# xm125_testing.net
KiCad netlist of a schematic drawn in EAGLE
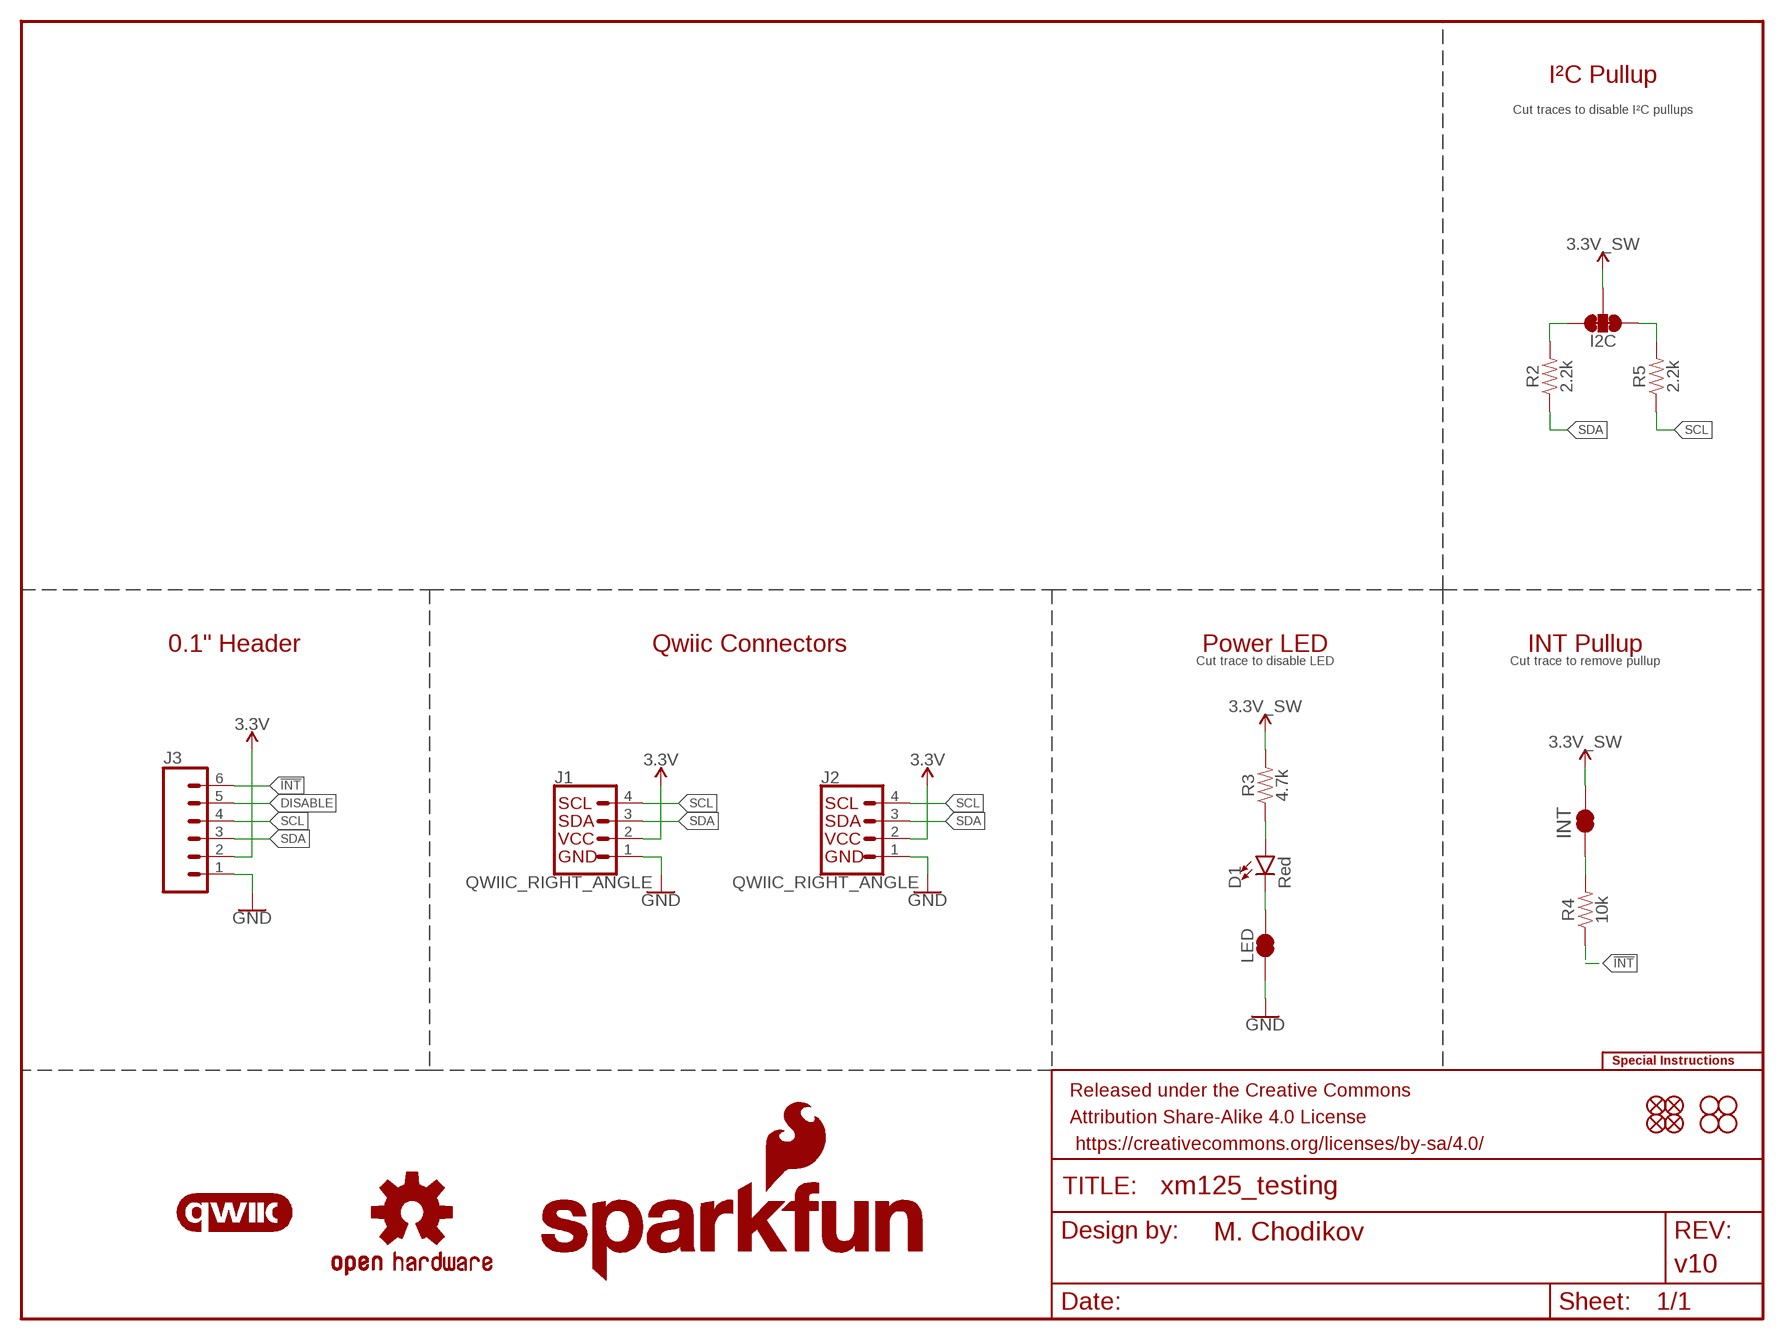
[diagram p0: schematic, sheet 1]

(export (version "E")
  (design (tool "Eeschema 10.0.6"))
  (components
    (comp (ref "D1")
      (value "Red")
      (footprint "eagle-import:LED-0603")
      (libsource (lib "eagle-import") (part "LED-RED_0603-KB"))
    )
    (comp (ref "FD1")
      (value "FIDUCIAL1X2")
      (footprint "eagle-import:FIDUCIAL-1X2")
      (libsource (lib "eagle-import") (part "FIDUCIAL1X2"))
    )
    (comp (ref "FD2")
      (value "FIDUCIAL1X2")
      (footprint "eagle-import:FIDUCIAL-1X2")
      (libsource (lib "eagle-import") (part "FIDUCIAL1X2"))
    )
    (comp (ref "FD3")
      (value "FIDUCIAL1X2")
      (footprint "eagle-import:FIDUCIAL-1X2")
      (libsource (lib "eagle-import") (part "FIDUCIAL1X2"))
    )
    (comp (ref "FD4")
      (value "FIDUCIAL1X2")
      (footprint "eagle-import:FIDUCIAL-1X2")
      (libsource (lib "eagle-import") (part "FIDUCIAL1X2"))
    )
    (comp (ref "FRAME1")
      (value "FRAME-LETTER")
      (footprint "eagle-import:CREATIVE_COMMONS")
      (fields (field (name "DESIGNER") "M. Chodikov") (field (name "REV") "v10"))
      (libsource (lib "eagle-import") (part "FRAME-LETTER"))
    )
    (comp (ref "H1")
      (value "STAND-OFF")
      (footprint "eagle-import:STAND-OFF")
      (libsource (lib "eagle-import") (part "STAND-OFF"))
    )
    (comp (ref "H2")
      (value "STAND-OFF")
      (footprint "eagle-import:STAND-OFF")
      (libsource (lib "eagle-import") (part "STAND-OFF"))
    )
    (comp (ref "H3")
      (value "STAND-OFF")
      (footprint "eagle-import:STAND-OFF")
      (libsource (lib "eagle-import") (part "STAND-OFF"))
    )
    (comp (ref "H4")
      (value "STAND-OFF")
      (footprint "eagle-import:STAND-OFF")
      (libsource (lib "eagle-import") (part "STAND-OFF"))
    )
    (comp (ref "I2C")
      (value "JUMPER-SMT_3_2-NC_TRACE_SILK")
      (footprint "eagle-import:SMT-JUMPER_3_2-NC_TRACE_SILK")
      (libsource (lib "eagle-import") (part "JUMPER-SMT_3_2-NC_TRACE_SILK"))
    )
    (comp (ref "J1")
      (value "QWIIC_RIGHT_ANGLE")
      (footprint "eagle-import:JST04_1MM_RA")
      (libsource (lib "eagle-import") (part "QWIIC_CONNECTORJS-1MM"))
    )
    (comp (ref "J2")
      (value "QWIIC_RIGHT_ANGLE")
      (footprint "eagle-import:JST04_1MM_RA")
      (libsource (lib "eagle-import") (part "QWIIC_CONNECTORJS-1MM"))
    )
    (comp (ref "J3")
      (value "CONN_06NO_SILK_FEMALE_PTH")
      (footprint "eagle-import:1X06_NO_SILK")
      (libsource (lib "eagle-import") (part "CONN_06NO_SILK_FEMALE_PTH"))
    )
    (comp (ref "JP2")
      (value "JUMPER-SMT_2_NC_TRACE_SILK")
      (footprint "eagle-import:SMT-JUMPER_2_NC_TRACE_SILK")
      (libsource (lib "eagle-import") (part "JUMPER-SMT_2_NC_TRACE_SILK"))
    )
    (comp (ref "LED")
      (value "JUMPER-SMT_2_NC_TRACE_SILK")
      (footprint "eagle-import:SMT-JUMPER_2_NC_TRACE_SILK")
      (libsource (lib "eagle-import") (part "JUMPER-SMT_2_NC_TRACE_SILK"))
    )
    (comp (ref "LOGO1")
      (value "OSHW-LOGOS")
      (footprint "eagle-import:OSHW-LOGO-S")
      (libsource (lib "eagle-import") (part "OSHW-LOGOS"))
    )
    (comp (ref "LOGO2")
      (value "SFE_LOGO_NAME_FLAME.1_INCH")
      (footprint "eagle-import:SFE_LOGO_NAME_FLAME_.1")
      (libsource (lib "eagle-import") (part "SFE_LOGO_NAME_FLAME.1_INCH"))
    )
    (comp (ref "LOGO3")
      (value "QWIIC_LOGO_4MM")
      (footprint "eagle-import:QWIIC_4MM")
      (libsource (lib "eagle-import") (part "QWIIC_LOGO_4MM"))
    )
    (comp (ref "LOGO4")
      (value "SFE_LOGO_NAME8_MM")
      (footprint "eagle-import:SFE_LOGO_NAME_8MM")
      (libsource (lib "eagle-import") (part "SFE_LOGO_NAME8_MM"))
    )
    (comp (ref "LOGO5")
      (value "SPECIAL_INSTRUCTIONS-ORDERING")
      (footprint "eagle-import:ORDERING_INSTRUCTIONS")
      (libsource (lib "eagle-import") (part "SPECIAL_INSTRUCTIONS-ORDERING"))
    )
    (comp (ref "LOGO6")
      (value "SFE_LOGO_FLAME.1_INCH")
      (footprint "eagle-import:SFE_LOGO_FLAME_.1")
      (libsource (lib "eagle-import") (part "SFE_LOGO_FLAME.1_INCH"))
    )
    (comp (ref "R2")
      (value "2.2k")
      (footprint "eagle-import:0603")
      (libsource (lib "eagle-import") (part "2.2KOHM-0603-1/10W-1%"))
    )
    (comp (ref "R3")
      (value "4.7k")
      (footprint "eagle-import:0603")
      (libsource (lib "eagle-import") (part "4.7KOHM-0603-1/10W-1%"))
    )
    (comp (ref "R4")
      (value "10k")
      (footprint "eagle-import:0603")
      (libsource (lib "eagle-import") (part "10KOHM-0603-1/10W-1%"))
    )
    (comp (ref "R5")
      (value "2.2k")
      (footprint "eagle-import:0603")
      (libsource (lib "eagle-import") (part "2.2KOHM-0603-1/10W-1%"))
    )
  )
  (nets
    (net (code "1") (name "/~{INT}") (class "Default")
      (node (ref "J3") (pin "6") (pinfunction "6_6") (pintype "passive"))
      (node (ref "R4") (pin "1") (pinfunction "1_1") (pintype "passive"))
    )
    (net (code "2") (name "3.3V") (class "Default")
      (node (ref "J1") (pin "2") (pinfunction "2_2") (pintype "power_in"))
      (node (ref "J2") (pin "2") (pinfunction "2_2") (pintype "power_in"))
      (node (ref "J3") (pin "2") (pinfunction "2_2") (pintype "passive"))
    )
    (net (code "3") (name "3.3V_SW") (class "Default")
      (node (ref "I2C") (pin "2") (pinfunction "2_2") (pintype "passive"))
      (node (ref "JP2") (pin "2") (pinfunction "2_2") (pintype "passive"))
      (node (ref "R3") (pin "2") (pinfunction "2_2") (pintype "passive"))
    )
    (net (code "4") (name "DISABLE") (class "Default")
      (node (ref "J3") (pin "5") (pinfunction "5_5") (pintype "passive"))
    )
    (net (code "5") (name "GND") (class "Default")
      (node (ref "J1") (pin "1") (pinfunction "1_1") (pintype "power_in"))
      (node (ref "J2") (pin "1") (pinfunction "1_1") (pintype "power_in"))
      (node (ref "J3") (pin "1") (pinfunction "1_1") (pintype "passive"))
      (node (ref "LED") (pin "1") (pinfunction "1_1") (pintype "passive"))
    )
    (net (code "6") (name "Net-(D1-PadA)") (class "Default")
      (node (ref "D1") (pin "A") (pinfunction "A_A") (pintype "passive"))
      (node (ref "R3") (pin "1") (pinfunction "1_1") (pintype "passive"))
    )
    (net (code "7") (name "Net-(D1-PadC)") (class "Default")
      (node (ref "D1") (pin "C") (pinfunction "C_C") (pintype "passive"))
      (node (ref "LED") (pin "2") (pinfunction "2_2") (pintype "passive"))
    )
    (net (code "8") (name "Net-(I2C-Pad1)") (class "Default")
      (node (ref "I2C") (pin "1") (pinfunction "1_1") (pintype "passive"))
      (node (ref "R5") (pin "2") (pinfunction "2_2") (pintype "passive"))
    )
    (net (code "9") (name "Net-(I2C-Pad3)") (class "Default")
      (node (ref "I2C") (pin "3") (pinfunction "3_3") (pintype "passive"))
      (node (ref "R2") (pin "2") (pinfunction "2_2") (pintype "passive"))
    )
    (net (code "10") (name "Net-(JP2-Pad1)") (class "Default")
      (node (ref "JP2") (pin "1") (pinfunction "1_1") (pintype "passive"))
      (node (ref "R4") (pin "2") (pinfunction "2_2") (pintype "passive"))
    )
    (net (code "11") (name "SCL") (class "Default")
      (node (ref "J1") (pin "4") (pinfunction "4_4") (pintype "passive"))
      (node (ref "J2") (pin "4") (pinfunction "4_4") (pintype "passive"))
      (node (ref "J3") (pin "4") (pinfunction "4_4") (pintype "passive"))
      (node (ref "R5") (pin "1") (pinfunction "1_1") (pintype "passive"))
    )
    (net (code "12") (name "SDA") (class "Default")
      (node (ref "J1") (pin "3") (pinfunction "3_3") (pintype "passive"))
      (node (ref "J2") (pin "3") (pinfunction "3_3") (pintype "passive"))
      (node (ref "J3") (pin "3") (pinfunction "3_3") (pintype "passive"))
      (node (ref "R2") (pin "1") (pinfunction "1_1") (pintype "passive"))
    )
  )
)
